# SJH-5XDMount_sch.net
KiCad netlist of a schematic drawn in EAGLE
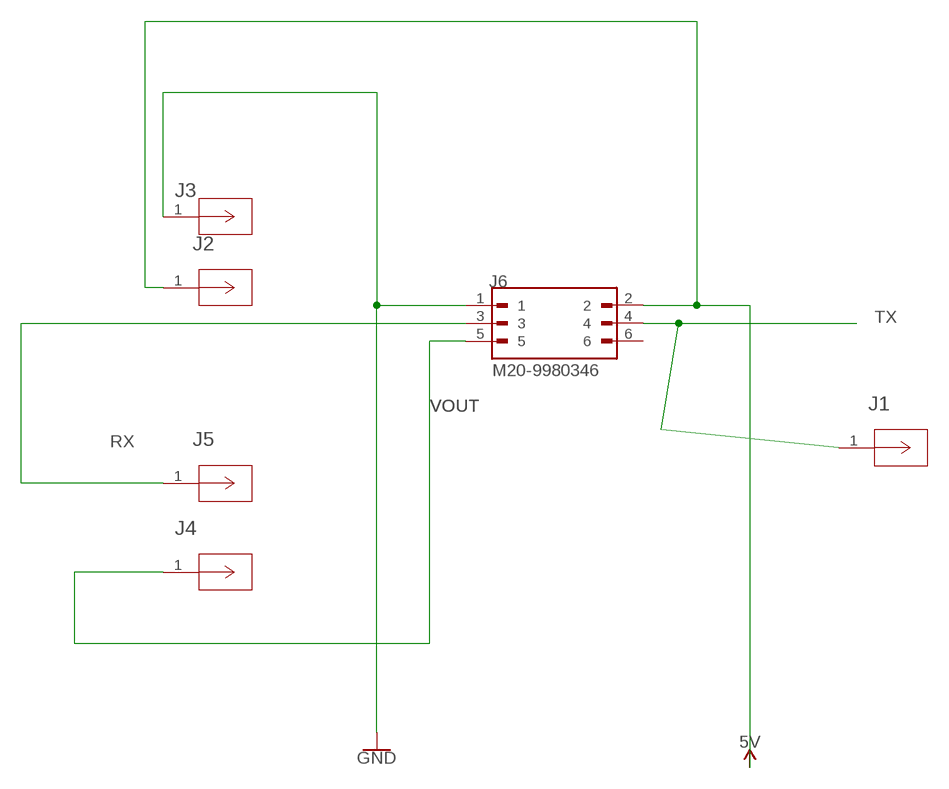
[diagram p0: schematic, sheet 1]

(export (version "E")
  (design (tool "Eeschema 10.0.6"))
  (components
    (comp (ref "J1")
      (value "450-3326-01-03-00")
      (footprint "eagle-import:CONN_450-3326-01-XX-00_CBN")
      (fields (field (name "COPYRIGHT") "Copyright (C) 2024 Ultra Librarian. All rights reserved."))
      (libsource (lib "eagle-import") (part "450-3326-01-03-00"))
    )
    (comp (ref "J2")
      (value "450-3326-01-03-00")
      (footprint "eagle-import:CONN_450-3326-01-XX-00_CBN")
      (fields (field (name "COPYRIGHT") "Copyright (C) 2024 Ultra Librarian. All rights reserved."))
      (libsource (lib "eagle-import") (part "450-3326-01-03-00"))
    )
    (comp (ref "J3")
      (value "450-3326-01-03-00")
      (footprint "eagle-import:CONN_450-3326-01-XX-00_CBN")
      (fields (field (name "COPYRIGHT") "Copyright (C) 2024 Ultra Librarian. All rights reserved."))
      (libsource (lib "eagle-import") (part "450-3326-01-03-00"))
    )
    (comp (ref "J4")
      (value "450-3326-01-03-00")
      (footprint "eagle-import:CONN_450-3326-01-XX-00_CBN")
      (fields (field (name "COPYRIGHT") "Copyright (C) 2024 Ultra Librarian. All rights reserved."))
      (libsource (lib "eagle-import") (part "450-3326-01-03-00"))
    )
    (comp (ref "J5")
      (value "450-3326-01-03-00")
      (footprint "eagle-import:CONN_450-3326-01-XX-00_CBN")
      (fields (field (name "COPYRIGHT") "Copyright (C) 2024 Ultra Librarian. All rights reserved."))
      (libsource (lib "eagle-import") (part "450-3326-01-03-00"))
    )
    (comp (ref "J6")
      (value "M20-9980346")
      (footprint "eagle-import:HARWIN_M20-9980346")
      (fields (field (name "MANUFACTURER") "HARWIN"))
      (libsource (lib "eagle-import") (part "M20-9980346"))
    )
  )
  (nets
    (net (code "1") (name "/RX") (class "Default")
      (node (ref "J5") (pin "1") (pinfunction "1_1") (pintype "passive"))
      (node (ref "J6") (pin "3") (pinfunction "3_3") (pintype "passive"))
    )
    (net (code "2") (name "/TX") (class "Default")
      (node (ref "J1") (pin "1") (pinfunction "1_1") (pintype "passive"))
      (node (ref "J6") (pin "4") (pinfunction "4_4") (pintype "passive"))
    )
    (net (code "3") (name "/VOUT") (class "Default")
      (node (ref "J4") (pin "1") (pinfunction "1_1") (pintype "passive"))
      (node (ref "J6") (pin "5") (pinfunction "5_5") (pintype "passive"))
    )
    (net (code "4") (name "5V") (class "Default")
      (node (ref "J2") (pin "1") (pinfunction "1_1") (pintype "passive"))
      (node (ref "J6") (pin "2") (pinfunction "2_2") (pintype "passive"))
    )
    (net (code "5") (name "GND") (class "Default")
      (node (ref "J3") (pin "1") (pinfunction "1_1") (pintype "passive"))
      (node (ref "J6") (pin "1") (pinfunction "1_1") (pintype "passive"))
    )
    (net (code "6") (name "unconnected-(J6-Pad6)") (class "Default")
      (node (ref "J6") (pin "6") (pinfunction "6_6") (pintype "passive"))
    )
  )
)
